# PCB.net
KiCad netlist of a schematic drawn in Altium Designer
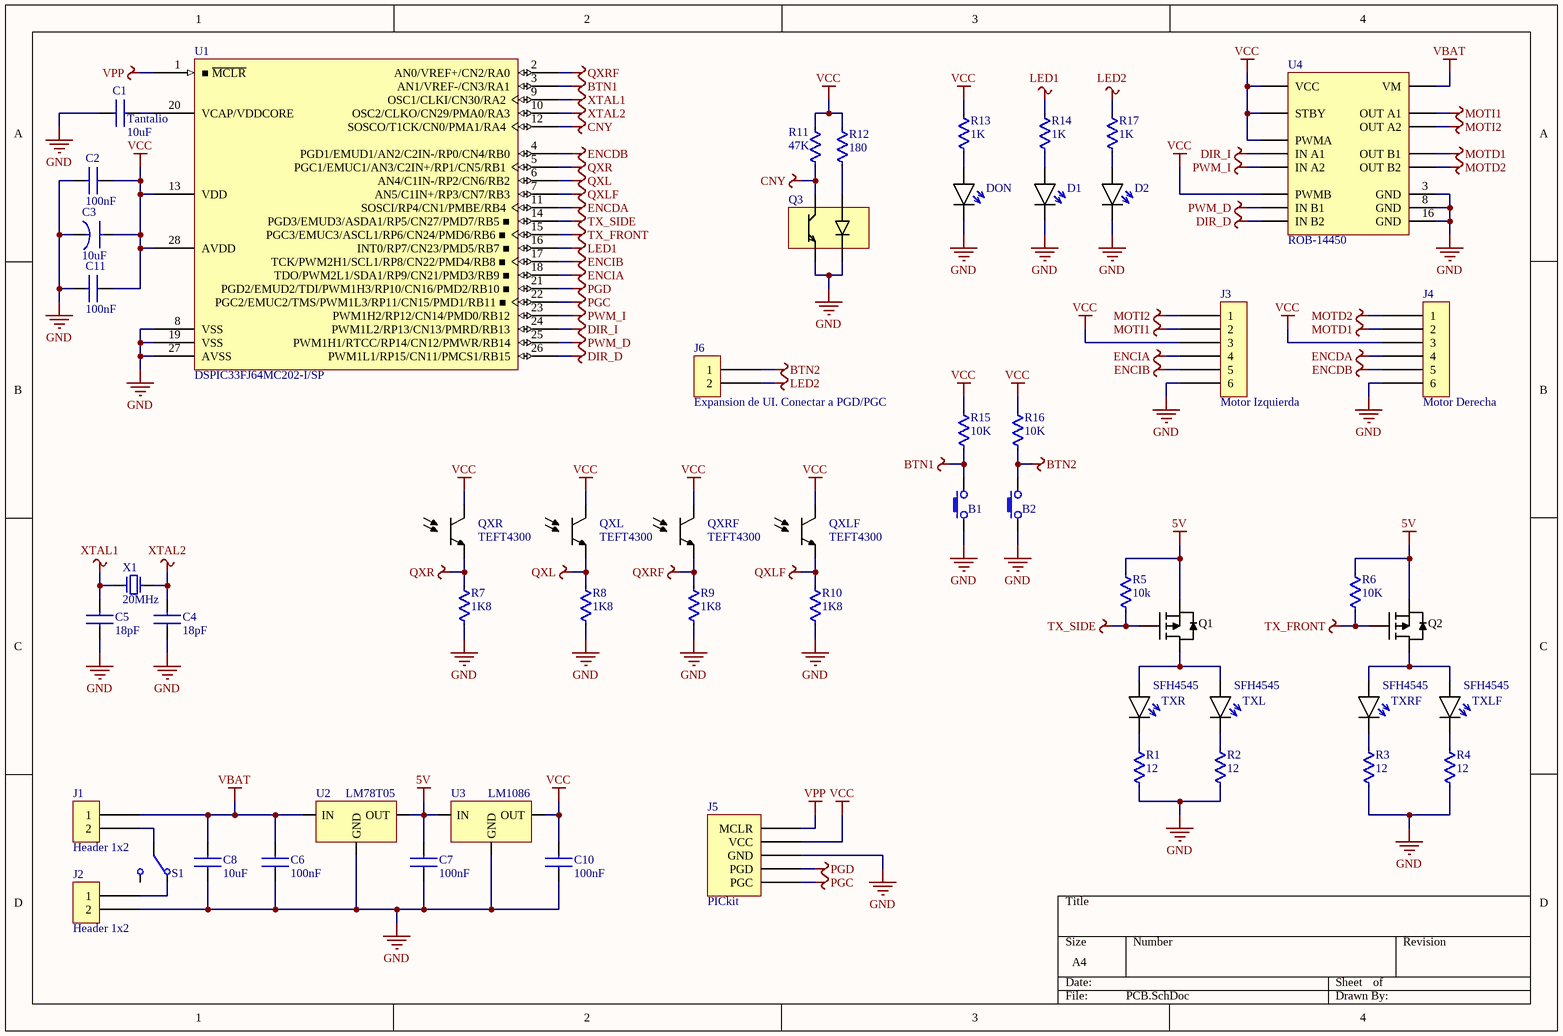
[diagram p0: PCB.SchDoc]

(export (version "E")
  (design (tool "Eeschema 10.0.6"))
  (components
    (comp (ref "B1")
      (value "BUTTON")
      (footprint "TACT_SWITCH-SMALL-4PIN")
      (libsource (lib "AltiumLibrary") (part "BUTTON"))
    )
    (comp (ref "B2")
      (value "BUTTON")
      (footprint "TACT_SWITCH-SMALL-4PIN")
      (libsource (lib "AltiumLibrary") (part "BUTTON"))
    )
    (comp (ref "C1")
      (value "Tantalio")
      (footprint "CAP-CER")
      (fields (field (name "ALTIUM_VALUE") "10uF"))
      (libsource (lib "AltiumLibrary") (part "CAP-CER"))
    )
    (comp (ref "C2")
      (value "100nF")
      (footprint "CAP-CER")
      (fields (field (name "Comment") "CAP-CER"))
      (libsource (lib "AltiumLibrary") (part "CAP-CER"))
    )
    (comp (ref "C3")
      (value "10uF")
      (footprint "CAP-ELEC-5x11x2mm")
      (fields (field (name "Comment") "CAP-ELEC"))
      (libsource (lib "AltiumLibrary") (part "CAP-ELEC"))
    )
    (comp (ref "C4")
      (value "18pF")
      (footprint "CAP-CER")
      (fields (field (name "Comment") "CAP-CER"))
      (libsource (lib "AltiumLibrary") (part "CAP-CER"))
    )
    (comp (ref "C5")
      (value "18pF")
      (footprint "CAP-CER")
      (fields (field (name "Comment") "CAP-CER"))
      (libsource (lib "AltiumLibrary") (part "CAP-CER"))
    )
    (comp (ref "C6")
      (value "100nF")
      (footprint "CAP-CER")
      (fields (field (name "Comment") "CAP-CER"))
      (libsource (lib "AltiumLibrary") (part "CAP-CER"))
    )
    (comp (ref "C7")
      (value "100nF")
      (footprint "CAP-CER")
      (fields (field (name "Comment") "CAP-CER"))
      (libsource (lib "AltiumLibrary") (part "CAP-CER"))
    )
    (comp (ref "C8")
      (value "10uF")
      (footprint "CAP-CER")
      (fields (field (name "Comment") "CAP-CER"))
      (libsource (lib "AltiumLibrary") (part "CAP-CER"))
    )
    (comp (ref "C10")
      (value "100nF")
      (footprint "CAP-CER")
      (fields (field (name "Comment") "CAP-CER"))
      (libsource (lib "AltiumLibrary") (part "CAP-CER"))
    )
    (comp (ref "C11")
      (value "100nF")
      (footprint "CAP-CER")
      (fields (field (name "Comment") "For pin"))
      (libsource (lib "AltiumLibrary") (part "CAP-CER"))
    )
    (comp (ref "D1")
      (value "LED")
      (footprint "LED-3MM-YELLOW")
      (libsource (lib "AltiumLibrary") (part "LED"))
    )
    (comp (ref "D2")
      (value "LED")
      (footprint "LED-3MM-YELLOW")
      (libsource (lib "AltiumLibrary") (part "LED"))
    )
    (comp (ref "DON") (value "LED") (footprint "LED-3MM-RED") (libsource (lib "AltiumLibrary") (part "LED")))
    (comp (ref "J1")
      (value "Header 1x2")
      (footprint "HEADER 1x2")
      (libsource (lib "AltiumLibrary") (part "Header 1x2"))
    )
    (comp (ref "J2")
      (value "Header 1x2")
      (footprint "HEADER 1x2")
      (libsource (lib "AltiumLibrary") (part "Header 1x2"))
    )
    (comp (ref "J3")
      (value "Motor Izquierda")
      (footprint "Header 1x6")
      (libsource (lib "AltiumLibrary") (part "Header 1x6"))
    )
    (comp (ref "J4")
      (value "Motor Derecha")
      (footprint "Header 1x6")
      (libsource (lib "AltiumLibrary") (part "Header 1x6"))
    )
    (comp (ref "J5")
      (value "PICkit")
      (footprint "Header 1x5")
      (libsource (lib "AltiumLibrary") (part "PICkit"))
    )
    (comp (ref "J6")
      (value "Expansion de UI. Conectar a PGD/PGC")
      (footprint "HEADER 1x2")
      (libsource (lib "AltiumLibrary") (part "Header 1x2"))
    )
    (comp (ref "Q1") (value "P-MOS") (footprint "TO-220") (libsource (lib "AltiumLibrary") (part "P-MOSFET")))
    (comp (ref "Q2") (value "P-MOS") (footprint "TO-220") (libsource (lib "AltiumLibrary") (part "P-MOSFET")))
    (comp (ref "Q3")
      (value "QRE1113GR")
      (footprint "QRE1113GR")
      (fields (field (name "MF") "ON Semiconductor"))
      (libsource (lib "AltiumLibrary") (part "QRE1113GR"))
    )
    (comp (ref "QXL")
      (value "TEFT4300")
      (footprint "PHOTO-NPN-2")
      (libsource (lib "AltiumLibrary") (part "PHOTO NPN"))
    )
    (comp (ref "QXLF")
      (value "TEFT4300")
      (footprint "PHOTO-NPN")
      (libsource (lib "AltiumLibrary") (part "PHOTO NPN"))
    )
    (comp (ref "QXR")
      (value "TEFT4300")
      (footprint "PHOTO-NPN")
      (libsource (lib "AltiumLibrary") (part "PHOTO NPN"))
    )
    (comp (ref "QXRF")
      (value "TEFT4300")
      (footprint "PHOTO-NPN-2")
      (libsource (lib "AltiumLibrary") (part "PHOTO NPN"))
    )
    (comp (ref "R1")
      (value "12")
      (footprint "RES-Axial-400mil")
      (fields (field (name "Comment") "RES"))
      (libsource (lib "AltiumLibrary") (part "RES"))
    )
    (comp (ref "R2")
      (value "12")
      (footprint "RES-Axial-400mil")
      (fields (field (name "Comment") "RES"))
      (libsource (lib "AltiumLibrary") (part "RES"))
    )
    (comp (ref "R3")
      (value "12")
      (footprint "RES-Axial-400mil")
      (fields (field (name "Comment") "RES"))
      (libsource (lib "AltiumLibrary") (part "RES"))
    )
    (comp (ref "R4")
      (value "12")
      (footprint "RES-Axial-400mil")
      (fields (field (name "Comment") "RES"))
      (libsource (lib "AltiumLibrary") (part "RES"))
    )
    (comp (ref "R5")
      (value "10k")
      (footprint "RES-Axial-400mil")
      (fields (field (name "Comment") "RES"))
      (libsource (lib "AltiumLibrary") (part "RES"))
    )
    (comp (ref "R6")
      (value "10K")
      (footprint "RES-Axial-400mil")
      (fields (field (name "Comment") "RES"))
      (libsource (lib "AltiumLibrary") (part "RES"))
    )
    (comp (ref "R7")
      (value "1K8")
      (footprint "RES VERTICAL")
      (fields (field (name "Comment") "RES"))
      (libsource (lib "AltiumLibrary") (part "RES"))
    )
    (comp (ref "R8")
      (value "1K8")
      (footprint "RES VERTICAL")
      (fields (field (name "Comment") "RES"))
      (libsource (lib "AltiumLibrary") (part "RES"))
    )
    (comp (ref "R9")
      (value "1K8")
      (footprint "RES-Axial-400mil")
      (fields (field (name "Comment") "RES"))
      (libsource (lib "AltiumLibrary") (part "RES"))
    )
    (comp (ref "R10")
      (value "1K8")
      (footprint "RES-Axial-400mil")
      (fields (field (name "Comment") "RES"))
      (libsource (lib "AltiumLibrary") (part "RES"))
    )
    (comp (ref "R11")
      (value "47K")
      (footprint "RES-Axial-400mil")
      (fields (field (name "Comment") "RES"))
      (libsource (lib "AltiumLibrary") (part "RES"))
    )
    (comp (ref "R12")
      (value "180")
      (footprint "RES-Axial-400mil")
      (fields (field (name "Comment") "RES"))
      (libsource (lib "AltiumLibrary") (part "RES"))
    )
    (comp (ref "R13")
      (value "1K")
      (footprint "RES-Axial-400mil")
      (fields (field (name "Comment") "RES"))
      (libsource (lib "AltiumLibrary") (part "RES"))
    )
    (comp (ref "R14")
      (value "1K")
      (footprint "RES VERTICAL")
      (fields (field (name "Comment") "RES"))
      (libsource (lib "AltiumLibrary") (part "RES"))
    )
    (comp (ref "R15")
      (value "10K")
      (footprint "RES-Axial-400mil")
      (fields (field (name "Comment") "RES"))
      (libsource (lib "AltiumLibrary") (part "RES"))
    )
    (comp (ref "R16")
      (value "10K")
      (footprint "RES-Axial-400mil")
      (fields (field (name "Comment") "RES"))
      (libsource (lib "AltiumLibrary") (part "RES"))
    )
    (comp (ref "R17")
      (value "1K")
      (footprint "RES VERTICAL")
      (fields (field (name "Comment") "RES"))
      (libsource (lib "AltiumLibrary") (part "RES"))
    )
    (comp (ref "S1")
      (value "SLIDE-SWITCH")
      (footprint "SWITCH")
      (libsource (lib "AltiumLibrary") (part "SLIDE-SWITCH"))
    )
    (comp (ref "TXL")
      (value "SFH4545")
      (footprint "LED-5MM-RED-90")
      (libsource (lib "AltiumLibrary") (part "LED"))
    )
    (comp (ref "TXLF")
      (value "SFH4545")
      (footprint "LED-5MM-RED-90")
      (libsource (lib "AltiumLibrary") (part "LED"))
    )
    (comp (ref "TXR")
      (value "SFH4545")
      (footprint "LED-5MM-RED-90-2")
      (libsource (lib "AltiumLibrary") (part "LED"))
    )
    (comp (ref "TXRF")
      (value "SFH4545")
      (footprint "LED-5MM-RED-90-2")
      (libsource (lib "AltiumLibrary") (part "LED"))
    )
    (comp (ref "U1")
      (value "DSPIC33FJ64MC202-I/SP")
      (footprint "DIP28")
      (fields (field (name "PUBLISHER") "Altium Limited"))
      (libsource (lib "AltiumLibrary") (part "DSPIC33FJ64MC202-I/SP"))
    )
    (comp (ref "U2") (value "LM78T05") (footprint "TO-220") (libsource (lib "AltiumLibrary") (part "LM78XX")))
    (comp (ref "U3") (value "LM1086") (footprint "TO-220") (libsource (lib "AltiumLibrary") (part "LM78XX")))
    (comp (ref "U4")
      (value "ROB-14450")
      (footprint "ROB-14450")
      (description "Power Management IC Development Tools SparkFun MotorDriver Dual TB6612FNG Head.")
      (libsource (lib "AltiumLibrary") (part "ROB-14450"))
    )
    (comp (ref "X1")
      (value "XTAL")
      (footprint "HC-49/S")
      (fields (field (name "FREQUENCY") "20MHz"))
      (libsource (lib "AltiumLibrary") (part "XTAL"))
    )
  )
  (nets
    (net (code "1") (name "5V") (class "Default")
      (node (ref "C7") (pin "2") (pintype "passive"))
      (node (ref "Q1") (pin "S") (pintype "passive"))
      (node (ref "Q2") (pin "S") (pintype "passive"))
      (node (ref "R5") (pin "2") (pintype "passive"))
      (node (ref "R6") (pin "2") (pintype "passive"))
      (node (ref "U2") (pin "3") (pinfunction "OUT_3") (pintype "power_in"))
      (node (ref "U3") (pin "1") (pinfunction "IN_1") (pintype "power_in"))
    )
    (net (code "2") (name "BTN1") (class "Default")
      (node (ref "B1") (pin "2") (pintype "passive"))
      (node (ref "R15") (pin "1") (pintype "passive"))
      (node (ref "U1") (pin "3") (pinfunction "AN1/VREF-/CN3/RA1_3") (pintype "bidirectional"))
    )
    (net (code "3") (name "BTN2") (class "Default")
      (node (ref "B2") (pin "2") (pintype "passive"))
      (node (ref "J6") (pin "1") (pinfunction "1_1") (pintype "passive"))
      (node (ref "R16") (pin "1") (pintype "passive"))
    )
    (net (code "4") (name "CNY") (class "Default")
      (node (ref "Q3") (pin "C") (pinfunction "C_C") (pintype "passive"))
      (node (ref "R11") (pin "1") (pintype "passive"))
      (node (ref "U1") (pin "12") (pinfunction "SOSCO/T1CK/CN0/PMA1/RA4_12") (pintype "bidirectional"))
    )
    (net (code "5") (name "DIR_D") (class "Default")
      (node (ref "U1") (pin "26") (pinfunction "PWM1L1/RP15/CN11/PMCS1/RB15_26") (pintype "bidirectional"))
      (node (ref "U4") (pin "14") (pinfunction "IN_B2_14") (pintype "passive"))
    )
    (net (code "6") (name "DIR_I") (class "Default")
      (node (ref "U1") (pin "24") (pinfunction "PWM1L2/RP13/CN13/PMRD/RB13_24") (pintype "bidirectional"))
      (node (ref "U4") (pin "11") (pinfunction "IN_A1_11") (pintype "passive"))
    )
    (net (code "7") (name "ENCDA") (class "Default")
      (node (ref "J4") (pin "4") (pinfunction "4_4") (pintype "passive"))
      (node (ref "U1") (pin "11") (pinfunction "SOSCI/RP4/CN1/PMBE/RB4_11") (pintype "bidirectional"))
    )
    (net (code "8") (name "ENCDB") (class "Default")
      (node (ref "J4") (pin "5") (pinfunction "5_5") (pintype "passive"))
      (node (ref "U1") (pin "4") (pinfunction "PGD1/EMUD1/AN2/C2IN-/RP0/CN4/RB0_4") (pintype "bidirectional"))
    )
    (net (code "9") (name "ENCIA") (class "Default")
      (node (ref "J3") (pin "4") (pinfunction "4_4") (pintype "passive"))
      (node (ref "U1") (pin "18") (pinfunction "TDO/PWM2L1/SDA1/RP9/CN21/PMD3/RB9_■_18") (pintype "bidirectional"))
    )
    (net (code "10") (name "ENCIB") (class "Default")
      (node (ref "J3") (pin "5") (pinfunction "5_5") (pintype "passive"))
      (node (ref "U1") (pin "17") (pinfunction "TCK/PWM2H1/SCL1/RP8/CN22/PMD4/RB8_■_17") (pintype "bidirectional"))
    )
    (net (code "11") (name "GND") (class "Default")
      (node (ref "B1") (pin "1") (pintype "passive"))
      (node (ref "B2") (pin "1") (pintype "passive"))
      (node (ref "C1") (pin "1") (pintype "passive"))
      (node (ref "C10") (pin "1") (pintype "passive"))
      (node (ref "C11") (pin "2") (pintype "passive"))
      (node (ref "C2") (pin "2") (pintype "passive"))
      (node (ref "C3") (pin "2") (pintype "passive"))
      (node (ref "C4") (pin "2") (pintype "passive"))
      (node (ref "C5") (pin "2") (pintype "passive"))
      (node (ref "C6") (pin "1") (pintype "passive"))
      (node (ref "C7") (pin "1") (pintype "passive"))
      (node (ref "C8") (pin "1") (pintype "passive"))
      (node (ref "D1") (pin "K") (pintype "passive"))
      (node (ref "D2") (pin "K") (pintype "passive"))
      (node (ref "DON") (pin "K") (pintype "passive"))
      (node (ref "J2") (pin "2") (pinfunction "2_2") (pintype "passive"))
      (node (ref "J3") (pin "6") (pinfunction "6_6") (pintype "passive"))
      (node (ref "J4") (pin "6") (pinfunction "6_6") (pintype "passive"))
      (node (ref "J5") (pin "3") (pinfunction "GND_3") (pintype "power_in"))
      (node (ref "Q3") (pin "E") (pinfunction "E_E") (pintype "passive"))
      (node (ref "Q3") (pin "K") (pinfunction "K_K") (pintype "passive"))
      (node (ref "R1") (pin "1") (pintype "passive"))
      (node (ref "R10") (pin "1") (pintype "passive"))
      (node (ref "R2") (pin "1") (pintype "passive"))
      (node (ref "R3") (pin "1") (pintype "passive"))
      (node (ref "R4") (pin "1") (pintype "passive"))
      (node (ref "R7") (pin "1") (pintype "passive"))
      (node (ref "R8") (pin "1") (pintype "passive"))
      (node (ref "R9") (pin "1") (pintype "passive"))
      (node (ref "U1") (pin "19") (pinfunction "VSS_19") (pintype "power_in"))
      (node (ref "U1") (pin "27") (pinfunction "AVSS_27") (pintype "power_in"))
      (node (ref "U1") (pin "8") (pinfunction "VSS_8") (pintype "power_in"))
      (node (ref "U2") (pin "2") (pinfunction "GND_2") (pintype "power_in"))
      (node (ref "U3") (pin "2") (pinfunction "GND_2") (pintype "power_in"))
      (node (ref "U4") (pin "16") (pinfunction "GND_16") (pintype "passive"))
      (node (ref "U4") (pin "3") (pinfunction "GND_3") (pintype "passive"))
      (node (ref "U4") (pin "8") (pinfunction "GND_8") (pintype "passive"))
    )
    (net (code "12") (name "LED1") (class "Default")
      (node (ref "R14") (pin "2") (pintype "passive"))
      (node (ref "U1") (pin "16") (pinfunction "INT0/RP7/CN23/PMD5/RB7_■_16") (pintype "bidirectional"))
    )
    (net (code "13") (name "LED2") (class "Default")
      (node (ref "J6") (pin "2") (pinfunction "2_2") (pintype "passive"))
      (node (ref "R17") (pin "2") (pintype "passive"))
    )
    (net (code "14") (name "MOTD1") (class "Default")
      (node (ref "J4") (pin "2") (pinfunction "2_2") (pintype "passive"))
      (node (ref "U4") (pin "7") (pinfunction "OUT_B1_7") (pintype "passive"))
    )
    (net (code "15") (name "MOTD2") (class "Default")
      (node (ref "J4") (pin "1") (pinfunction "1_1") (pintype "passive"))
      (node (ref "U4") (pin "6") (pinfunction "OUT_B2_6") (pintype "passive"))
    )
    (net (code "16") (name "MOTI1") (class "Default")
      (node (ref "J3") (pin "2") (pinfunction "2_2") (pintype "passive"))
      (node (ref "U4") (pin "4") (pinfunction "OUT_A1_4") (pintype "passive"))
    )
    (net (code "17") (name "MOTI2") (class "Default")
      (node (ref "J3") (pin "1") (pinfunction "1_1") (pintype "passive"))
      (node (ref "U4") (pin "5") (pinfunction "OUT_A2_5") (pintype "passive"))
    )
    (net (code "18") (name "Net-(D1-PadA)") (class "Default")
      (node (ref "D1") (pin "A") (pintype "passive"))
      (node (ref "R14") (pin "1") (pintype "passive"))
    )
    (net (code "19") (name "Net-(D2-PadA)") (class "Default")
      (node (ref "D2") (pin "A") (pintype "passive"))
      (node (ref "R17") (pin "1") (pintype "passive"))
    )
    (net (code "20") (name "Net-(DON-PadA)") (class "Default")
      (node (ref "DON") (pin "A") (pintype "passive"))
      (node (ref "R13") (pin "1") (pintype "passive"))
    )
    (net (code "21") (name "Net-(J1-Pad2)") (class "Default")
      (node (ref "J1") (pin "2") (pinfunction "2_2") (pintype "passive"))
      (node (ref "S1") (pin "2") (pintype "power_in"))
    )
    (net (code "22") (name "Net-(J2-Pad1)") (class "Default")
      (node (ref "J2") (pin "1") (pinfunction "1_1") (pintype "passive"))
      (node (ref "S1") (pin "1") (pintype "power_in"))
    )
    (net (code "23") (name "Net-(Q1-PadD)") (class "Default")
      (node (ref "Q1") (pin "D") (pintype "passive"))
      (node (ref "TXL") (pin "A") (pintype "passive"))
      (node (ref "TXR") (pin "A") (pintype "passive"))
    )
    (net (code "24") (name "Net-(Q2-PadD)") (class "Default")
      (node (ref "Q2") (pin "D") (pintype "passive"))
      (node (ref "TXLF") (pin "A") (pintype "passive"))
      (node (ref "TXRF") (pin "A") (pintype "passive"))
    )
    (net (code "25") (name "Net-(Q3-PadA)") (class "Default")
      (node (ref "Q3") (pin "A") (pinfunction "A_A") (pintype "passive"))
      (node (ref "R12") (pin "1") (pintype "passive"))
    )
    (net (code "26") (name "Net-(R1-Pad2)") (class "Default")
      (node (ref "R1") (pin "2") (pintype "passive"))
      (node (ref "TXR") (pin "K") (pintype "passive"))
    )
    (net (code "27") (name "Net-(R2-Pad2)") (class "Default")
      (node (ref "R2") (pin "2") (pintype "passive"))
      (node (ref "TXL") (pin "K") (pintype "passive"))
    )
    (net (code "28") (name "Net-(R3-Pad2)") (class "Default")
      (node (ref "R3") (pin "2") (pintype "passive"))
      (node (ref "TXRF") (pin "K") (pintype "passive"))
    )
    (net (code "29") (name "Net-(R4-Pad2)") (class "Default")
      (node (ref "R4") (pin "2") (pintype "passive"))
      (node (ref "TXLF") (pin "K") (pintype "passive"))
    )
    (net (code "30") (name "Net-(U1-VCAP{slash}VDDCORE)") (class "Default")
      (node (ref "C1") (pin "2") (pintype "passive"))
      (node (ref "U1") (pin "20") (pinfunction "VCAP/VDDCORE_20") (pintype "power_in"))
    )
    (net (code "31") (name "PGC") (class "Default")
      (node (ref "J5") (pin "5") (pinfunction "PGC_5") (pintype "passive"))
      (node (ref "U1") (pin "22") (pinfunction "PGC2/EMUC2/TMS/PWM1L3/RP11/CN15/PMD1/RB11_■_22") (pintype "bidirectional"))
    )
    (net (code "32") (name "PGD") (class "Default")
      (node (ref "J5") (pin "4") (pinfunction "PGD_4") (pintype "passive"))
      (node (ref "U1") (pin "21") (pinfunction "PGD2/EMUD2/TDI/PWM1H3/RP10/CN16/PMD2/RB10_■_21") (pintype "bidirectional"))
    )
    (net (code "33") (name "PWM_D") (class "Default")
      (node (ref "U1") (pin "25") (pinfunction "PWM1H1/RTCC/RP14/CN12/PMWR/RB14_25") (pintype "bidirectional"))
      (node (ref "U4") (pin "13") (pinfunction "IN_B1_13") (pintype "passive"))
    )
    (net (code "34") (name "PWM_I") (class "Default")
      (node (ref "U1") (pin "23") (pinfunction "PWM1H2/RP12/CN14/PMD0/RB12_23") (pintype "bidirectional"))
      (node (ref "U4") (pin "10") (pinfunction "IN_A2_10") (pintype "passive"))
    )
    (net (code "35") (name "QXL") (class "Default")
      (node (ref "QXL") (pin "E") (pinfunction "E_E") (pintype "passive"))
      (node (ref "R8") (pin "2") (pintype "passive"))
      (node (ref "U1") (pin "6") (pinfunction "AN4/C1IN-/RP2/CN6/RB2_6") (pintype "bidirectional"))
    )
    (net (code "36") (name "QXLF") (class "Default")
      (node (ref "QXLF") (pin "E") (pinfunction "E_E") (pintype "passive"))
      (node (ref "R10") (pin "2") (pintype "passive"))
      (node (ref "U1") (pin "7") (pinfunction "AN5/C1IN+/RP3/CN7/RB3_7") (pintype "bidirectional"))
    )
    (net (code "37") (name "QXR") (class "Default")
      (node (ref "QXR") (pin "E") (pinfunction "E_E") (pintype "passive"))
      (node (ref "R7") (pin "2") (pintype "passive"))
      (node (ref "U1") (pin "5") (pinfunction "PGC1/EMUC1/AN3/C2IN+/RP1/CN5/RB1_5") (pintype "bidirectional"))
    )
    (net (code "38") (name "QXRF") (class "Default")
      (node (ref "QXRF") (pin "E") (pinfunction "E_E") (pintype "passive"))
      (node (ref "R9") (pin "2") (pintype "passive"))
      (node (ref "U1") (pin "2") (pinfunction "AN0/VREF+/CN2/RA0_2") (pintype "bidirectional"))
    )
    (net (code "39") (name "TX_FRONT") (class "Default")
      (node (ref "Q2") (pin "G") (pintype "passive"))
      (node (ref "R6") (pin "1") (pintype "passive"))
      (node (ref "U1") (pin "15") (pinfunction "PGC3/EMUC3/ASCL1/RP6/CN24/PMD6/RB6_■_15") (pintype "bidirectional"))
    )
    (net (code "40") (name "TX_SIDE") (class "Default")
      (node (ref "Q1") (pin "G") (pintype "passive"))
      (node (ref "R5") (pin "1") (pintype "passive"))
      (node (ref "U1") (pin "14") (pinfunction "PGD3/EMUD3/ASDA1/RP5/CN27/PMD7/RB5_■_14") (pintype "bidirectional"))
    )
    (net (code "41") (name "VBAT") (class "Default")
      (node (ref "C6") (pin "2") (pintype "passive"))
      (node (ref "C8") (pin "2") (pintype "passive"))
      (node (ref "J1") (pin "1") (pinfunction "1_1") (pintype "passive"))
      (node (ref "U2") (pin "1") (pinfunction "IN_1") (pintype "power_in"))
      (node (ref "U4") (pin "1") (pinfunction "VM_1") (pintype "passive"))
    )
    (net (code "42") (name "VCC") (class "Default")
      (node (ref "C10") (pin "2") (pintype "passive"))
      (node (ref "C11") (pin "1") (pintype "passive"))
      (node (ref "C2") (pin "1") (pintype "passive"))
      (node (ref "C3") (pin "1") (pintype "passive"))
      (node (ref "J3") (pin "3") (pinfunction "3_3") (pintype "passive"))
      (node (ref "J4") (pin "3") (pinfunction "3_3") (pintype "passive"))
      (node (ref "J5") (pin "2") (pinfunction "VCC_2") (pintype "power_in"))
      (node (ref "QXL") (pin "C") (pinfunction "C_C") (pintype "passive"))
      (node (ref "QXLF") (pin "C") (pinfunction "C_C") (pintype "passive"))
      (node (ref "QXR") (pin "C") (pinfunction "C_C") (pintype "passive"))
      (node (ref "QXRF") (pin "C") (pinfunction "C_C") (pintype "passive"))
      (node (ref "R11") (pin "2") (pintype "passive"))
      (node (ref "R12") (pin "2") (pintype "passive"))
      (node (ref "R13") (pin "2") (pintype "passive"))
      (node (ref "R15") (pin "2") (pintype "passive"))
      (node (ref "R16") (pin "2") (pintype "passive"))
      (node (ref "U1") (pin "13") (pinfunction "VDD_13") (pintype "power_in"))
      (node (ref "U1") (pin "28") (pinfunction "AVDD_28") (pintype "power_in"))
      (node (ref "U3") (pin "3") (pinfunction "OUT_3") (pintype "power_in"))
      (node (ref "U4") (pin "12") (pinfunction "STBY_12") (pintype "passive"))
      (node (ref "U4") (pin "15") (pinfunction "PWMB_15") (pintype "passive"))
      (node (ref "U4") (pin "2") (pinfunction "VCC_2") (pintype "passive"))
      (node (ref "U4") (pin "9") (pinfunction "PWMA_9") (pintype "passive"))
    )
    (net (code "43") (name "VPP") (class "Default")
      (node (ref "J5") (pin "1") (pinfunction "MCLR_1") (pintype "passive"))
      (node (ref "U1") (pin "1") (pinfunction "■_~{MCLR}_1") (pintype "input"))
    )
    (net (code "44") (name "XTAL1") (class "Default")
      (node (ref "C5") (pin "1") (pintype "passive"))
      (node (ref "U1") (pin "9") (pinfunction "OSC1/CLKI/CN30/RA2_9") (pintype "bidirectional"))
      (node (ref "X1") (pin "1") (pintype "passive"))
    )
    (net (code "45") (name "XTAL2") (class "Default")
      (node (ref "C4") (pin "1") (pintype "passive"))
      (node (ref "U1") (pin "10") (pinfunction "OSC2/CLKO/CN29/PMA0/RA3_10") (pintype "bidirectional"))
      (node (ref "X1") (pin "2") (pintype "passive"))
    )
    (net (code "46") (name "unconnected-(S1-Pad3)") (class "Default")
      (node (ref "S1") (pin "3") (pintype "power_in"))
    )
  )
)
